# 48V_Converter.net
KiCad netlist of a schematic drawn in Altium Designer
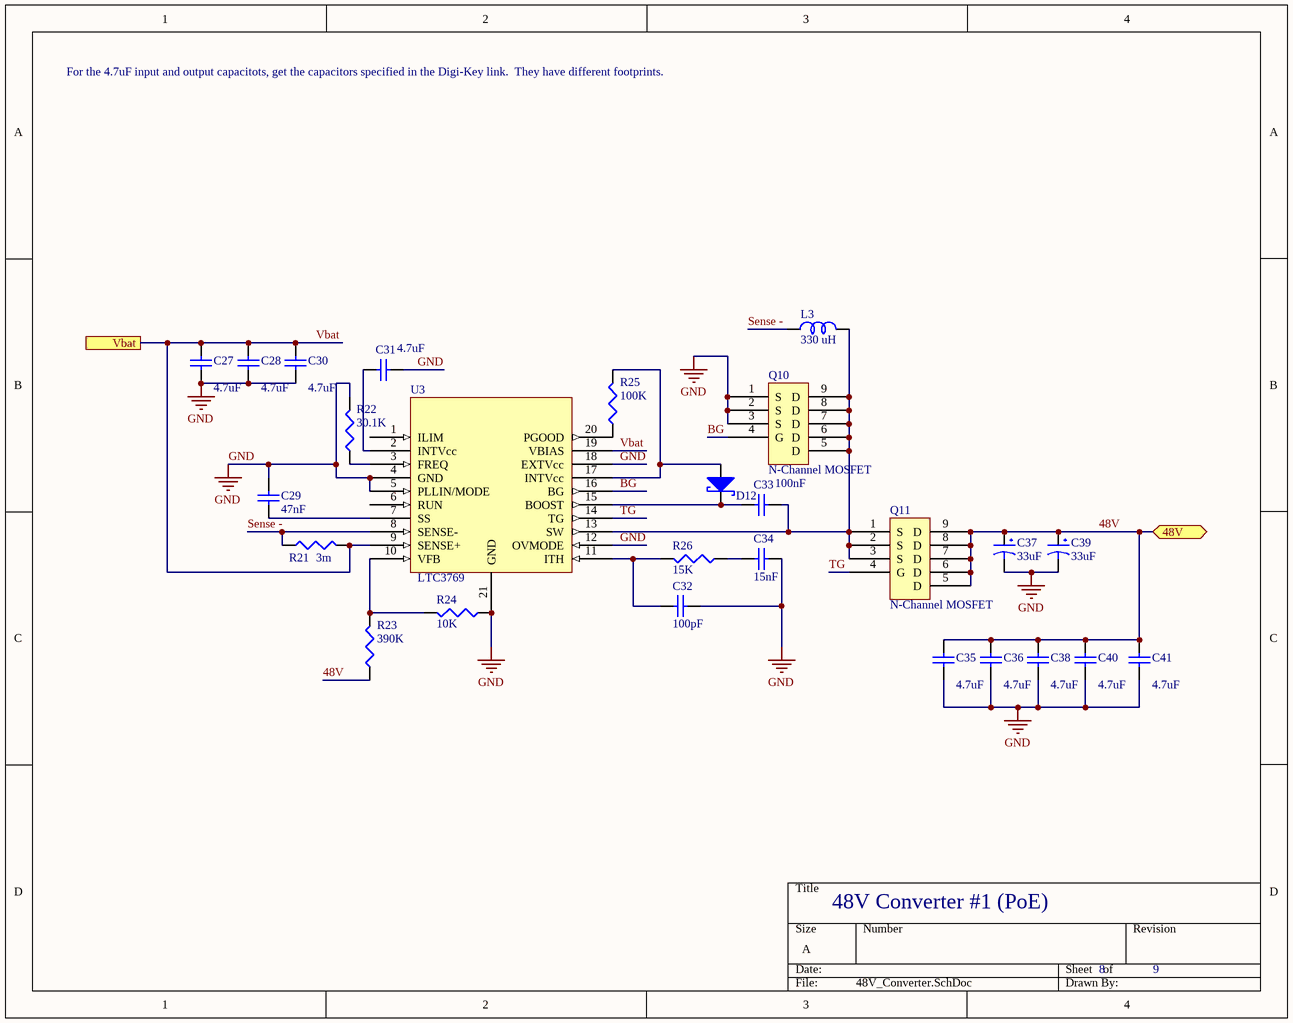
[diagram p0: 48V_Converter.SchDoc]

(export (version "E")
  (design (tool "Eeschema 10.0.6"))
  (components
    (comp (ref "C27")
      (value "4.7uF")
      (footprint "C1210")
      (description "Capacitor (Semiconductor SIM Model)")
      (fields (field (name "Comment") "HMK325C7475KN-TE") (field (name "PUBLISHER") "Altium Limited"))
      (libsource (lib "Miscellaneous Devices") (part "Cap Semi"))
    )
    (comp (ref "C28")
      (value "4.7uF")
      (footprint "C1210")
      (description "Capacitor (Semiconductor SIM Model)")
      (fields (field (name "Comment") "HMK325C7475KN-TE") (field (name "PUBLISHER") "Altium Limited"))
      (libsource (lib "Miscellaneous Devices") (part "Cap Semi"))
    )
    (comp (ref "C29")
      (value "47nF")
      (footprint "C1206")
      (description "Capacitor (Semiconductor SIM Model)")
      (fields (field (name "Comment") "Cap Semi") (field (name "PUBLISHER") "Altium Limited"))
      (libsource (lib "Miscellaneous Devices") (part "Cap Semi"))
    )
    (comp (ref "C30")
      (value "4.7uF")
      (footprint "C1210")
      (description "Capacitor (Semiconductor SIM Model)")
      (fields (field (name "Comment") "HMK325C7475KN-TE") (field (name "PUBLISHER") "Altium Limited"))
      (libsource (lib "Miscellaneous Devices") (part "Cap Semi"))
    )
    (comp (ref "C31")
      (value "4.7uF")
      (footprint "C1206")
      (description "Capacitor (Semiconductor SIM Model)")
      (fields (field (name "Comment") "Cap Semi") (field (name "PUBLISHER") "Altium Limited"))
      (libsource (lib "Miscellaneous Devices") (part "Cap Semi"))
    )
    (comp (ref "C32")
      (value "100pF")
      (footprint "C1206")
      (description "Capacitor (Semiconductor SIM Model)")
      (fields (field (name "Comment") "Cap Semi") (field (name "PUBLISHER") "Altium Limited"))
      (libsource (lib "Miscellaneous Devices") (part "Cap Semi"))
    )
    (comp (ref "C33")
      (value "100nF")
      (footprint "C1206")
      (description "Capacitor (Semiconductor SIM Model)")
      (fields (field (name "Comment") "Cap Semi") (field (name "PUBLISHER") "Altium Limited"))
      (libsource (lib "Miscellaneous Devices") (part "Cap Semi"))
    )
    (comp (ref "C34")
      (value "15nF")
      (footprint "C1206")
      (description "Capacitor (Semiconductor SIM Model)")
      (fields (field (name "Comment") "Cap Semi") (field (name "PUBLISHER") "Altium Limited"))
      (libsource (lib "Miscellaneous Devices") (part "Cap Semi"))
    )
    (comp (ref "C35")
      (value "4.7uF")
      (footprint "C1210")
      (description "Capacitor (Semiconductor SIM Model)")
      (fields (field (name "Comment") "HMK325C7475KN-TE") (field (name "PUBLISHER") "Altium Limited"))
      (libsource (lib "Miscellaneous Devices") (part "Cap Semi"))
    )
    (comp (ref "C36")
      (value "4.7uF")
      (footprint "C1210")
      (description "Capacitor (Semiconductor SIM Model)")
      (fields (field (name "Comment") "HMK325C7475KN-TE") (field (name "PUBLISHER") "Altium Limited"))
      (libsource (lib "Miscellaneous Devices") (part "Cap Semi"))
    )
    (comp (ref "C37")
      (value "33uF")
      (footprint "UUX1J330MNL6GS")
      (description "CAP ALUM 33UF 20% 63V SMD")
      (libsource (lib "Power_Embedded_Board_Library") (part "UUX1J330MNL6GS"))
    )
    (comp (ref "C38")
      (value "4.7uF")
      (footprint "C1210")
      (description "Capacitor (Semiconductor SIM Model)")
      (fields (field (name "Comment") "HMK325C7475KN-TE") (field (name "PUBLISHER") "Altium Limited"))
      (libsource (lib "Miscellaneous Devices") (part "Cap Semi"))
    )
    (comp (ref "C39")
      (value "33uF")
      (footprint "UUX1J330MNL6GS")
      (description "CAP ALUM 33UF 20% 63V SMD")
      (libsource (lib "Power_Embedded_Board_Library") (part "UUX1J330MNL6GS"))
    )
    (comp (ref "C40")
      (value "4.7uF")
      (footprint "C1210")
      (description "Capacitor (Semiconductor SIM Model)")
      (fields (field (name "Comment") "HMK325C7475KN-TE") (field (name "PUBLISHER") "Altium Limited"))
      (libsource (lib "Miscellaneous Devices") (part "Cap Semi"))
    )
    (comp (ref "C41")
      (value "4.7uF")
      (footprint "C1210")
      (description "Capacitor (Semiconductor SIM Model)")
      (fields (field (name "Comment") "HMK325C7475KN-TE") (field (name "PUBLISHER") "Altium Limited"))
      (libsource (lib "Miscellaneous Devices") (part "Cap Semi"))
    )
    (comp (ref "D12")
      (value "SCHOTTKY")
      (footprint "BAS170W")
      (description "DIODE SCHOTTKY 70V 70MA SOD323-2")
      (libsource (lib "Power_Embedded_Board_Library") (part "BAS170W"))
    )
    (comp (ref "L3")
      (value "330 uH")
      (footprint "PQ2617BHA-330K")
      (description "33µH Shielded Wirewound Inductor 28A 2.5mOhm Max Nonstandard")
      (libsource (lib "Power_Embedded_Board_Library") (part "PQ2617BHA-330K"))
    )
    (comp (ref "Q10")
      (value "N-Channel MOSFET")
      (footprint "BSC028N06LS3")
      (libsource (lib "Power_Embedded_Board_Library") (part "BSC028N06LS3"))
    )
    (comp (ref "Q11")
      (value "N-Channel MOSFET")
      (footprint "BSC028N06LS3")
      (libsource (lib "Power_Embedded_Board_Library") (part "BSC028N06LS3"))
    )
    (comp (ref "R21")
      (value "3m")
      (footprint "12Z-2010")
      (description "Resistor")
      (fields (field (name "Comment") "Res3") (field (name "PUBLISHER") "Altium Limited"))
      (libsource (lib "Miscellaneous Devices") (part "Res3"))
    )
    (comp (ref "R22")
      (value "30.1K")
      (footprint "J1-0603")
      (description "Resistor")
      (fields (field (name "Comment") "Res3") (field (name "PUBLISHER") "Altium Limited"))
      (libsource (lib "Miscellaneous Devices") (part "Res3"))
    )
    (comp (ref "R23")
      (value "390K")
      (footprint "J1-0603")
      (description "Resistor")
      (fields (field (name "Comment") "Res3") (field (name "PUBLISHER") "Altium Limited"))
      (libsource (lib "Miscellaneous Devices") (part "Res3"))
    )
    (comp (ref "R24")
      (value "10K")
      (footprint "J1-0603")
      (description "Resistor")
      (fields (field (name "Comment") "Res3") (field (name "PUBLISHER") "Altium Limited"))
      (libsource (lib "Miscellaneous Devices") (part "Res3"))
    )
    (comp (ref "R25")
      (value "100K")
      (footprint "J1-0603")
      (description "Resistor")
      (fields (field (name "Comment") "Res3") (field (name "PUBLISHER") "Altium Limited"))
      (libsource (lib "Miscellaneous Devices") (part "Res3"))
    )
    (comp (ref "R26")
      (value "15K")
      (footprint "J1-0603")
      (description "Resistor")
      (fields (field (name "Comment") "Res3") (field (name "PUBLISHER") "Altium Limited"))
      (libsource (lib "Miscellaneous Devices") (part "Res3"))
    )
    (comp (ref "U3")
      (value "LTC3769")
      (footprint "LTC3769")
      (description "48V Switching converter")
      (libsource (lib "Power_Embedded_Board_Library") (part "LTC3769"))
    )
  )
  (nets
    (net (code "1") (name "/48V") (class "Default")
      (node (ref "C35") (pin "2") (pinfunction "2_2") (pintype "passive"))
      (node (ref "C36") (pin "2") (pinfunction "2_2") (pintype "passive"))
      (node (ref "C37") (pin "1") (pinfunction "1_1") (pintype "passive"))
      (node (ref "C38") (pin "2") (pinfunction "2_2") (pintype "passive"))
      (node (ref "C39") (pin "1") (pinfunction "1_1") (pintype "passive"))
      (node (ref "C40") (pin "2") (pinfunction "2_2") (pintype "passive"))
      (node (ref "C41") (pin "2") (pinfunction "2_2") (pintype "passive"))
      (node (ref "Q11") (pin "5") (pinfunction "D_5") (pintype "passive"))
      (node (ref "Q11") (pin "6") (pinfunction "D_6") (pintype "passive"))
      (node (ref "Q11") (pin "7") (pinfunction "D_7") (pintype "passive"))
      (node (ref "Q11") (pin "8") (pinfunction "D_8") (pintype "passive"))
      (node (ref "Q11") (pin "9") (pinfunction "D_9") (pintype "passive"))
      (node (ref "R23") (pin "1") (pinfunction "1_1") (pintype "passive"))
    )
    (net (code "2") (name "/BG") (class "Default")
      (node (ref "Q10") (pin "4") (pinfunction "G_4") (pintype "passive"))
      (node (ref "U3") (pin "16") (pinfunction "BG_16") (pintype "output"))
    )
    (net (code "3") (name "/Sense -") (class "Default")
      (node (ref "L3") (pin "2") (pinfunction "2_2") (pintype "passive"))
      (node (ref "R21") (pin "1") (pinfunction "1_1") (pintype "passive"))
      (node (ref "U3") (pin "8") (pinfunction "SENSE-_8") (pintype "input"))
    )
    (net (code "4") (name "/TG") (class "Default")
      (node (ref "Q11") (pin "4") (pinfunction "G_4") (pintype "passive"))
      (node (ref "U3") (pin "14") (pinfunction "TG_14") (pintype "output"))
    )
    (net (code "5") (name "/Vbat") (class "Default")
      (node (ref "C27") (pin "2") (pinfunction "2_2") (pintype "passive"))
      (node (ref "C28") (pin "2") (pinfunction "2_2") (pintype "passive"))
      (node (ref "C30") (pin "2") (pinfunction "2_2") (pintype "passive"))
      (node (ref "R21") (pin "2") (pinfunction "2_2") (pintype "passive"))
      (node (ref "U3") (pin "19") (pinfunction "VBIAS_19") (pintype "power_in"))
      (node (ref "U3") (pin "9") (pinfunction "SENSE+_9") (pintype "input"))
    )
    (net (code "6") (name "GND") (class "Default")
      (node (ref "C27") (pin "1") (pinfunction "1_1") (pintype "passive"))
      (node (ref "C28") (pin "1") (pinfunction "1_1") (pintype "passive"))
      (node (ref "C29") (pin "2") (pinfunction "2_2") (pintype "passive"))
      (node (ref "C30") (pin "1") (pinfunction "1_1") (pintype "passive"))
      (node (ref "C31") (pin "1") (pinfunction "1_1") (pintype "passive"))
      (node (ref "C32") (pin "1") (pinfunction "1_1") (pintype "passive"))
      (node (ref "C34") (pin "1") (pinfunction "1_1") (pintype "passive"))
      (node (ref "C35") (pin "1") (pinfunction "1_1") (pintype "passive"))
      (node (ref "C36") (pin "1") (pinfunction "1_1") (pintype "passive"))
      (node (ref "C37") (pin "2") (pinfunction "2_2") (pintype "passive"))
      (node (ref "C38") (pin "1") (pinfunction "1_1") (pintype "passive"))
      (node (ref "C39") (pin "2") (pinfunction "2_2") (pintype "passive"))
      (node (ref "C40") (pin "1") (pinfunction "1_1") (pintype "passive"))
      (node (ref "C41") (pin "1") (pinfunction "1_1") (pintype "passive"))
      (node (ref "Q10") (pin "1") (pinfunction "S_1") (pintype "passive"))
      (node (ref "Q10") (pin "2") (pinfunction "S_2") (pintype "passive"))
      (node (ref "Q10") (pin "3") (pinfunction "S_3") (pintype "passive"))
      (node (ref "R22") (pin "2") (pinfunction "2_2") (pintype "passive"))
      (node (ref "R24") (pin "1") (pinfunction "1_1") (pintype "passive"))
      (node (ref "U3") (pin "12") (pinfunction "OVMODE_12") (pintype "input"))
      (node (ref "U3") (pin "18") (pinfunction "EXTVcc_18") (pintype "power_in"))
      (node (ref "U3") (pin "21") (pinfunction "GND_21") (pintype "power_in"))
      (node (ref "U3") (pin "4") (pinfunction "GND_4") (pintype "power_in"))
      (node (ref "U3") (pin "5") (pinfunction "PLLIN/MODE_5") (pintype "input"))
    )
    (net (code "7") (name "Net-(C31-Pad2)") (class "Default")
      (node (ref "C31") (pin "2") (pinfunction "2_2") (pintype "passive"))
      (node (ref "U3") (pin "2") (pinfunction "INTVcc_2") (pintype "power_in"))
    )
    (net (code "8") (name "Net-(C34-Pad2)") (class "Default")
      (node (ref "C34") (pin "2") (pinfunction "2_2") (pintype "passive"))
      (node (ref "R26") (pin "1") (pinfunction "1_1") (pintype "passive"))
    )
    (net (code "9") (name "Net-(D12-Anode)") (class "Default")
      (node (ref "D12") (pin "A") (pinfunction "Anode_A") (pintype "passive"))
      (node (ref "R25") (pin "2") (pinfunction "2_2") (pintype "passive"))
      (node (ref "U3") (pin "17") (pinfunction "INTVcc_17") (pintype "power_in"))
    )
    (net (code "10") (name "Net-(D12-Cathode)") (class "Default")
      (node (ref "C33") (pin "2") (pinfunction "2_2") (pintype "passive"))
      (node (ref "D12") (pin "K") (pinfunction "Cathode_K") (pintype "passive"))
      (node (ref "U3") (pin "15") (pinfunction "BOOST_15") (pintype "output"))
    )
    (net (code "11") (name "Net-(U3-FREQ)") (class "Default")
      (node (ref "R22") (pin "1") (pinfunction "1_1") (pintype "passive"))
      (node (ref "U3") (pin "3") (pinfunction "FREQ_3") (pintype "input"))
    )
    (net (code "12") (name "Net-(U3-ITH)") (class "Default")
      (node (ref "C32") (pin "2") (pinfunction "2_2") (pintype "passive"))
      (node (ref "R26") (pin "2") (pinfunction "2_2") (pintype "passive"))
      (node (ref "U3") (pin "11") (pinfunction "ITH_11") (pintype "input"))
    )
    (net (code "13") (name "Net-(U3-PGOOD)") (class "Default")
      (node (ref "R25") (pin "1") (pinfunction "1_1") (pintype "passive"))
      (node (ref "U3") (pin "20") (pinfunction "PGOOD_20") (pintype "output"))
    )
    (net (code "14") (name "Net-(U3-SS)") (class "Default")
      (node (ref "C29") (pin "1") (pinfunction "1_1") (pintype "passive"))
      (node (ref "U3") (pin "7") (pinfunction "SS_7") (pintype "passive"))
    )
    (net (code "15") (name "Net-(U3-SW)") (class "Default")
      (node (ref "C33") (pin "1") (pinfunction "1_1") (pintype "passive"))
      (node (ref "L3") (pin "1") (pinfunction "1_1") (pintype "passive"))
      (node (ref "Q10") (pin "5") (pinfunction "D_5") (pintype "passive"))
      (node (ref "Q10") (pin "6") (pinfunction "D_6") (pintype "passive"))
      (node (ref "Q10") (pin "7") (pinfunction "D_7") (pintype "passive"))
      (node (ref "Q10") (pin "8") (pinfunction "D_8") (pintype "passive"))
      (node (ref "Q10") (pin "9") (pinfunction "D_9") (pintype "passive"))
      (node (ref "Q11") (pin "1") (pinfunction "S_1") (pintype "passive"))
      (node (ref "Q11") (pin "2") (pinfunction "S_2") (pintype "passive"))
      (node (ref "Q11") (pin "3") (pinfunction "S_3") (pintype "passive"))
      (node (ref "U3") (pin "13") (pinfunction "SW_13") (pintype "output"))
    )
    (net (code "16") (name "Net-(U3-VFB)") (class "Default")
      (node (ref "R23") (pin "2") (pinfunction "2_2") (pintype "passive"))
      (node (ref "R24") (pin "2") (pinfunction "2_2") (pintype "passive"))
      (node (ref "U3") (pin "10") (pinfunction "VFB_10") (pintype "input"))
    )
    (net (code "17") (name "unconnected-(U3-ILIM-Pad1)") (class "Default")
      (node (ref "U3") (pin "1") (pinfunction "ILIM_1") (pintype "input"))
    )
    (net (code "18") (name "unconnected-(U3-RUN-Pad6)") (class "Default")
      (node (ref "U3") (pin "6") (pinfunction "RUN_6") (pintype "input"))
    )
  )
)
